# TL431_VoltageSupply.net
KiCad netlist of a schematic drawn in EAGLE
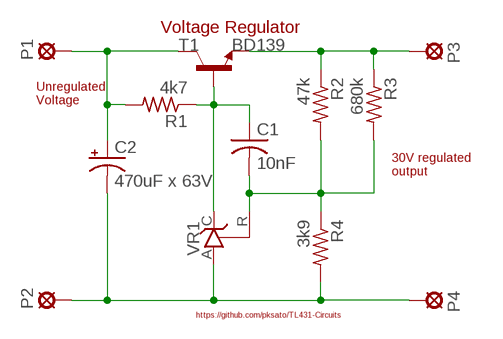
[diagram p0: schematic, sheet 1]

(export (version "E")
  (design (tool "Eeschema 10.0.6"))
  (components
    (comp (ref "C1")
      (value "10nF")
      (footprint "eagle-import:C050-024X044")
      (libsource (lib "eagle-import") (part "C-US050-024X044"))
    )
    (comp (ref "C2")
      (value "470uF x 63V")
      (footprint "eagle-import:E5-13")
      (libsource (lib "eagle-import") (part "CPOL-USE5-13"))
    )
    (comp (ref "P1")
      (value "LSP10")
      (footprint "eagle-import:LSP10")
      (libsource (lib "eagle-import") (part "LSP10"))
    )
    (comp (ref "P2")
      (value "LSP10")
      (footprint "eagle-import:LSP10")
      (libsource (lib "eagle-import") (part "LSP10"))
    )
    (comp (ref "P3")
      (value "LSP10")
      (footprint "eagle-import:LSP10")
      (libsource (lib "eagle-import") (part "LSP10"))
    )
    (comp (ref "P4")
      (value "LSP10")
      (footprint "eagle-import:LSP10")
      (libsource (lib "eagle-import") (part "LSP10"))
    )
    (comp (ref "R1")
      (value "4k7")
      (footprint "eagle-import:0207_10")
      (libsource (lib "eagle-import") (part "R-US_0207/10"))
    )
    (comp (ref "R2")
      (value "47k")
      (footprint "eagle-import:0207_10")
      (libsource (lib "eagle-import") (part "R-US_0207/10"))
    )
    (comp (ref "R3")
      (value "680k")
      (footprint "eagle-import:0207_10")
      (libsource (lib "eagle-import") (part "R-US_0207/10"))
    )
    (comp (ref "R4")
      (value "3k9")
      (footprint "eagle-import:0207_10")
      (libsource (lib "eagle-import") (part "R-US_0207/10"))
    )
    (comp (ref "T1")
      (value "BD139")
      (footprint "eagle-import:TO126")
      (libsource (lib "eagle-import") (part "BD139"))
    )
    (comp (ref "VR1")
      (value "TL431CLP")
      (footprint "eagle-import:TO92-CLP")
      (libsource (lib "eagle-import") (part "TL431CLP"))
    )
  )
  (nets
    (net (code "1") (name "Net-(C1-Pad2)") (class "Default")
      (node (ref "C1") (pin "2") (pinfunction "2_2") (pintype "passive"))
      (node (ref "R2") (pin "2") (pinfunction "2_2") (pintype "passive"))
      (node (ref "R3") (pin "2") (pinfunction "2_2") (pintype "passive"))
      (node (ref "R4") (pin "1") (pinfunction "1_1") (pintype "passive"))
      (node (ref "VR1") (pin "R") (pinfunction "R_R") (pintype "passive"))
    )
    (net (code "2") (name "Net-(C2-Pad-)") (class "Default")
      (node (ref "C2") (pin "-") (pinfunction "-_-") (pintype "passive"))
      (node (ref "P2") (pin "MP") (pinfunction "MP_MP") (pintype "passive"))
      (node (ref "P4") (pin "MP") (pinfunction "MP_MP") (pintype "passive"))
      (node (ref "R4") (pin "2") (pinfunction "2_2") (pintype "passive"))
      (node (ref "VR1") (pin "A") (pinfunction "A_A") (pintype "passive"))
    )
    (net (code "3") (name "Net-(T1-B)") (class "Default")
      (node (ref "C1") (pin "1") (pinfunction "1_1") (pintype "passive"))
      (node (ref "R1") (pin "1") (pinfunction "1_1") (pintype "passive"))
      (node (ref "T1") (pin "3") (pinfunction "B_3") (pintype "passive"))
      (node (ref "VR1") (pin "C") (pinfunction "C_C") (pintype "passive"))
    )
    (net (code "4") (name "Net-(T1-C)") (class "Default")
      (node (ref "C2") (pin "+") (pinfunction "+_+") (pintype "passive"))
      (node (ref "P1") (pin "MP") (pinfunction "MP_MP") (pintype "passive"))
      (node (ref "R1") (pin "2") (pinfunction "2_2") (pintype "passive"))
      (node (ref "T1") (pin "2") (pinfunction "C_2") (pintype "passive"))
    )
    (net (code "5") (name "Net-(T1-E)") (class "Default")
      (node (ref "P3") (pin "MP") (pinfunction "MP_MP") (pintype "passive"))
      (node (ref "R2") (pin "1") (pinfunction "1_1") (pintype "passive"))
      (node (ref "R3") (pin "1") (pinfunction "1_1") (pintype "passive"))
      (node (ref "T1") (pin "1") (pinfunction "E_1") (pintype "passive"))
    )
  )
)
